# Apollo4-BluePlus-Module_rev_b_v7.net
KiCad netlist of a schematic drawn in EAGLE
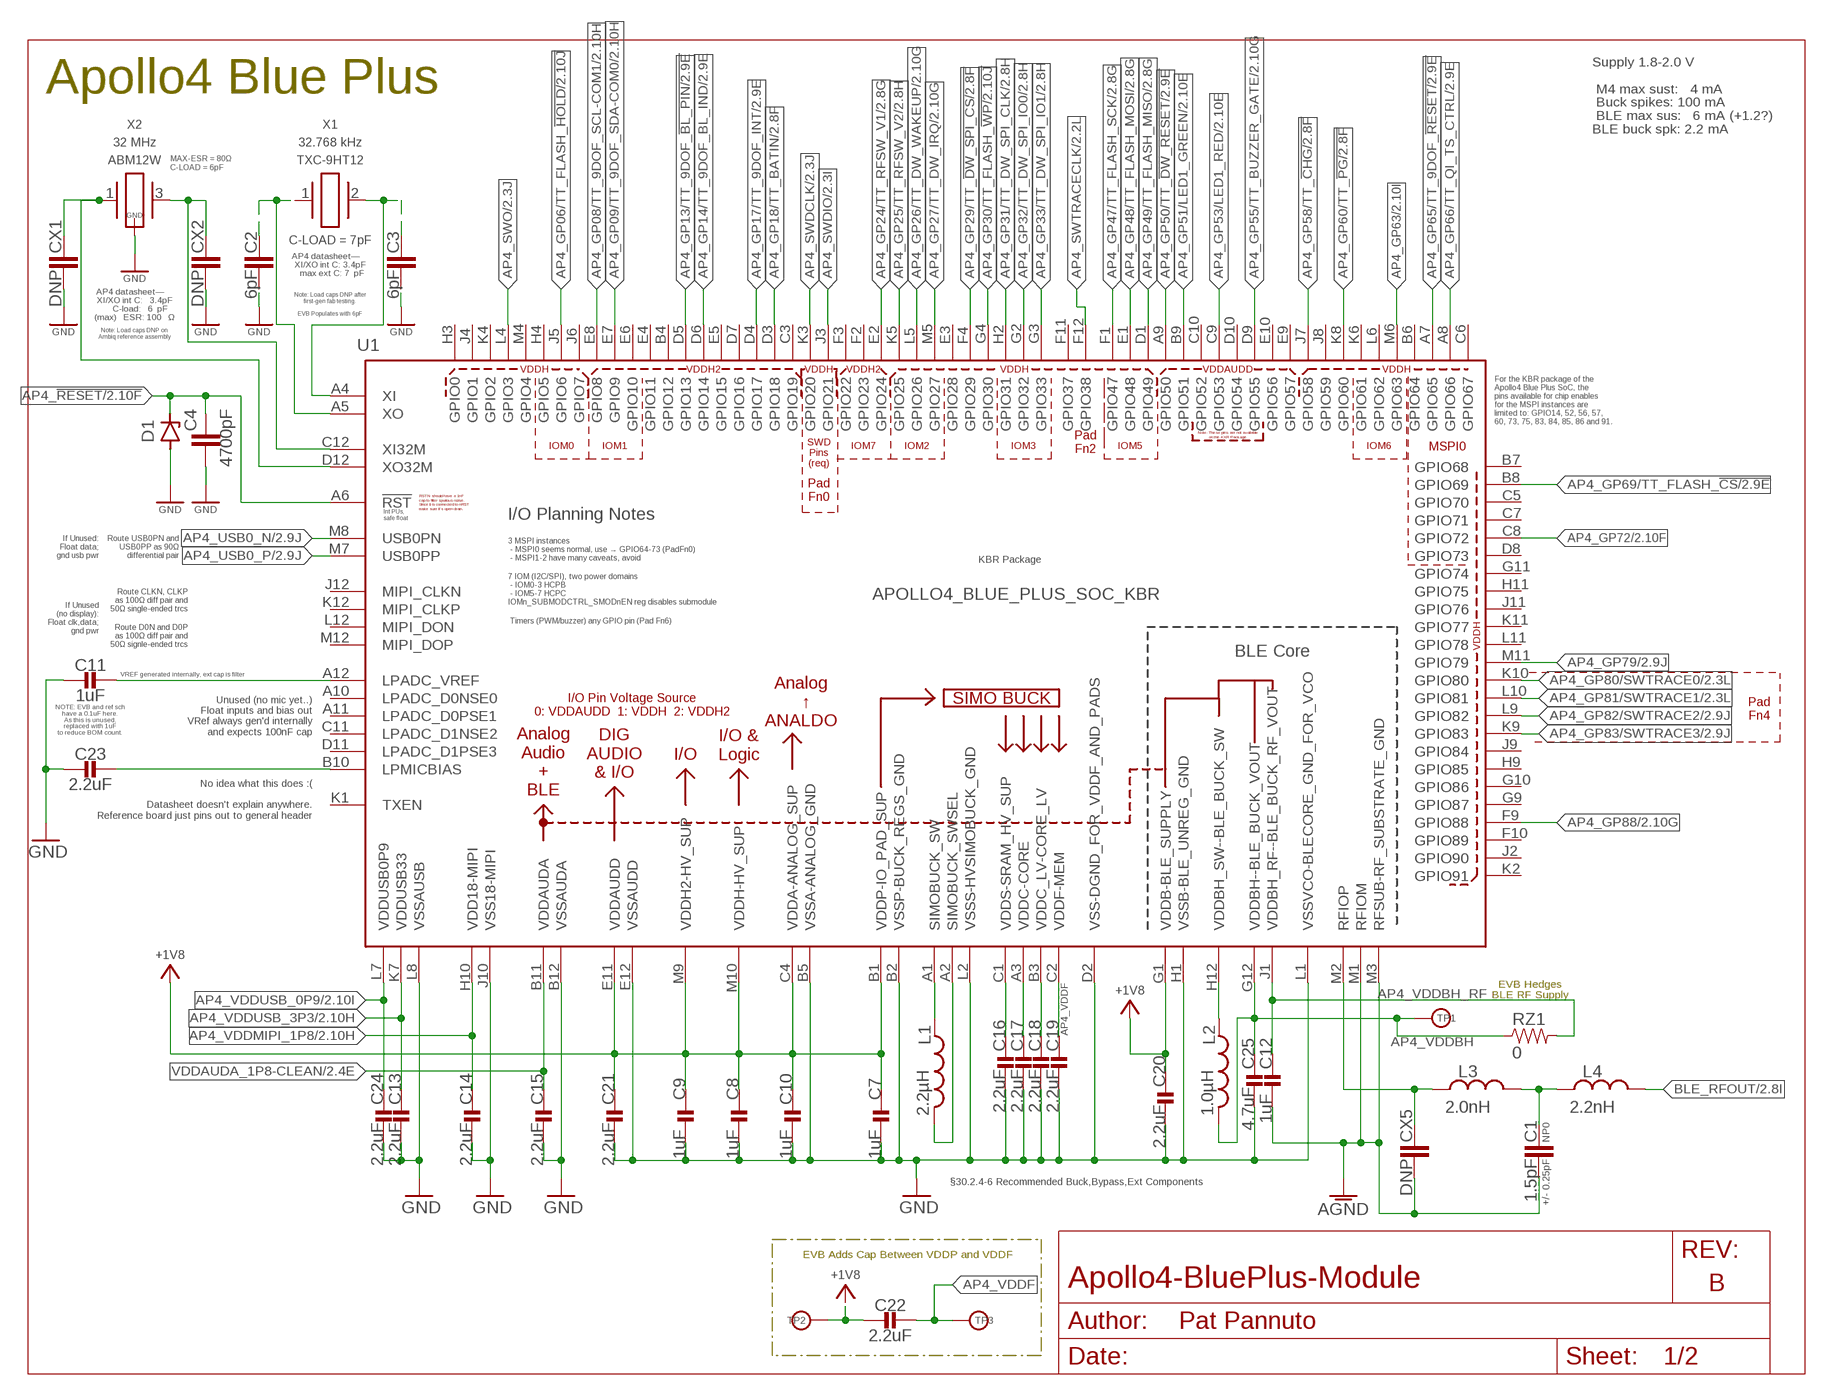
[diagram p0: schematic, sheet 1]
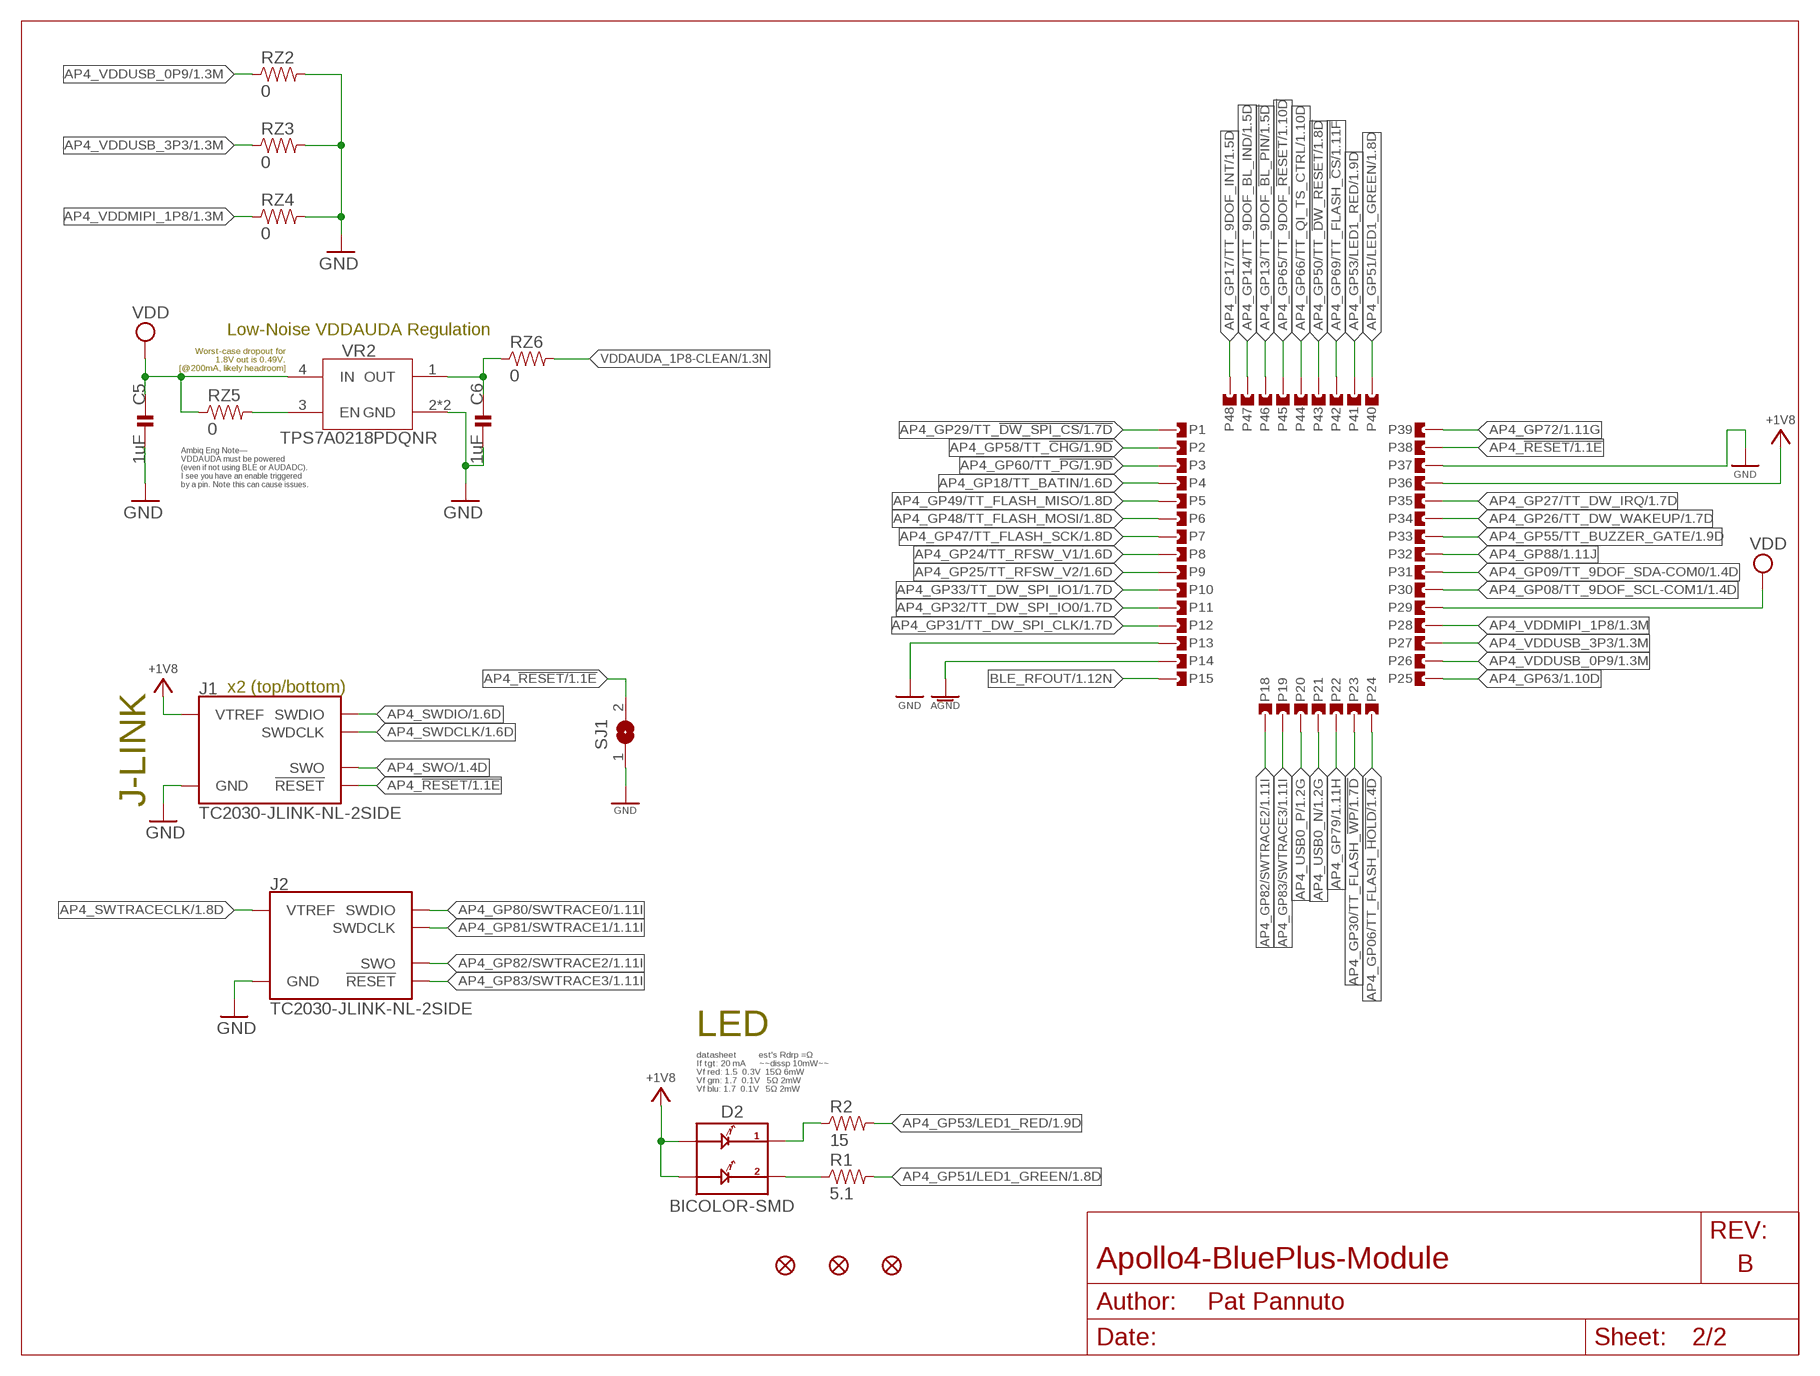
[diagram p1: schematic, sheet 2]

(export (version "E")
  (design (tool "Eeschema 10.0.6"))
  (components
    (comp (ref "C5")
      (value "1uF")
      (footprint "eagle-import:0201_CAP")
      (fields (field (name "MANUFACTURER") "Murata") (field (name "MPN") "GRM033R61A105ME44D"))
      (libsource (lib "eagle-import") (part "passives_20904581_CAPACITOR0201_CAP"))
    )
    (comp (ref "C6")
      (value "1uF")
      (footprint "eagle-import:0201_CAP")
      (fields (field (name "MANUFACTURER") "Murata") (field (name "MPN") "GRM033R61A105ME44D"))
      (libsource (lib "eagle-import") (part "passives_20904581_CAPACITOR0201_CAP"))
    )
    (comp (ref "D2")
      (value "BICOLOR-SMD")
      (footprint "eagle-import:LED-0606")
      (fields (field (name "MPN") "MCL0606FRD1GR1T"))
      (libsource (lib "eagle-import") (part "BICOLOR-SMD"))
    )
    (comp (ref "FD1")
      (value "FIDUCIALUFIDUCIAL")
      (footprint "eagle-import:FIDUCIAL-MICRO")
      (libsource (lib "eagle-import") (part "FIDUCIALUFIDUCIAL"))
    )
    (comp (ref "FD2")
      (value "FIDUCIALUFIDUCIAL")
      (footprint "eagle-import:FIDUCIAL-MICRO")
      (libsource (lib "eagle-import") (part "FIDUCIALUFIDUCIAL"))
    )
    (comp (ref "FD3")
      (value "FIDUCIALUFIDUCIAL")
      (footprint "eagle-import:FIDUCIAL-MICRO")
      (libsource (lib "eagle-import") (part "FIDUCIALUFIDUCIAL"))
    )
    (comp (ref "J1")
      (value "TC2030-JLINK-NL-2SIDE")
      (footprint "eagle-import:TC2030-IDC-NL-2SIDE")
      (libsource (lib "eagle-import") (part "TC2030-JLINK-NL-2SIDE"))
    )
    (comp (ref "J2")
      (value "TC2030-JLINK-NL-2SIDE")
      (footprint "eagle-import:TC2030-IDC-NL-2SIDE")
      (libsource (lib "eagle-import") (part "TC2030-JLINK-NL-2SIDE"))
    )
    (comp (ref "P1")
      (value "CASTELLATION4L")
      (footprint "eagle-import:CASTELLATION-0.55MM_DRILL-4L")
      (libsource (lib "eagle-import") (part "CASTELLATION4L"))
    )
    (comp (ref "P2")
      (value "CASTELLATION4L")
      (footprint "eagle-import:CASTELLATION-0.55MM_DRILL-4L")
      (libsource (lib "eagle-import") (part "CASTELLATION4L"))
    )
    (comp (ref "P3")
      (value "CASTELLATION4L")
      (footprint "eagle-import:CASTELLATION-0.55MM_DRILL-4L")
      (libsource (lib "eagle-import") (part "CASTELLATION4L"))
    )
    (comp (ref "P4")
      (value "CASTELLATION4L")
      (footprint "eagle-import:CASTELLATION-0.55MM_DRILL-4L")
      (libsource (lib "eagle-import") (part "CASTELLATION4L"))
    )
    (comp (ref "P5")
      (value "CASTELLATION4L")
      (footprint "eagle-import:CASTELLATION-0.55MM_DRILL-4L")
      (libsource (lib "eagle-import") (part "CASTELLATION4L"))
    )
    (comp (ref "P6")
      (value "CASTELLATION4L")
      (footprint "eagle-import:CASTELLATION-0.55MM_DRILL-4L")
      (libsource (lib "eagle-import") (part "CASTELLATION4L"))
    )
    (comp (ref "P7")
      (value "CASTELLATION4L")
      (footprint "eagle-import:CASTELLATION-0.55MM_DRILL-4L")
      (libsource (lib "eagle-import") (part "CASTELLATION4L"))
    )
    (comp (ref "P8")
      (value "CASTELLATION4L")
      (footprint "eagle-import:CASTELLATION-0.55MM_DRILL-4L")
      (libsource (lib "eagle-import") (part "CASTELLATION4L"))
    )
    (comp (ref "P9")
      (value "CASTELLATION4L")
      (footprint "eagle-import:CASTELLATION-0.55MM_DRILL-4L")
      (libsource (lib "eagle-import") (part "CASTELLATION4L"))
    )
    (comp (ref "P10")
      (value "CASTELLATION4L")
      (footprint "eagle-import:CASTELLATION-0.55MM_DRILL-4L")
      (libsource (lib "eagle-import") (part "CASTELLATION4L"))
    )
    (comp (ref "P11")
      (value "CASTELLATION4L")
      (footprint "eagle-import:CASTELLATION-0.55MM_DRILL-4L")
      (libsource (lib "eagle-import") (part "CASTELLATION4L"))
    )
    (comp (ref "P12")
      (value "CASTELLATION4L")
      (footprint "eagle-import:CASTELLATION-0.55MM_DRILL-4L")
      (libsource (lib "eagle-import") (part "CASTELLATION4L"))
    )
    (comp (ref "P13")
      (value "CASTELLATION4L")
      (footprint "eagle-import:CASTELLATION-0.55MM_DRILL-4L")
      (libsource (lib "eagle-import") (part "CASTELLATION4L"))
    )
    (comp (ref "P14")
      (value "CASTELLATION4L")
      (footprint "eagle-import:CASTELLATION-0.55MM_DRILL-4L")
      (libsource (lib "eagle-import") (part "CASTELLATION4L"))
    )
    (comp (ref "P15")
      (value "CASTELLATION4L")
      (footprint "eagle-import:CASTELLATION-0.55MM_DRILL-4L")
      (libsource (lib "eagle-import") (part "CASTELLATION4L"))
    )
    (comp (ref "P18")
      (value "CASTELLATION4L")
      (footprint "eagle-import:CASTELLATION-0.55MM_DRILL-4L")
      (libsource (lib "eagle-import") (part "CASTELLATION4L"))
    )
    (comp (ref "P19")
      (value "CASTELLATION4L")
      (footprint "eagle-import:CASTELLATION-0.55MM_DRILL-4L")
      (libsource (lib "eagle-import") (part "CASTELLATION4L"))
    )
    (comp (ref "P20")
      (value "CASTELLATION4L")
      (footprint "eagle-import:CASTELLATION-0.55MM_DRILL-4L")
      (libsource (lib "eagle-import") (part "CASTELLATION4L"))
    )
    (comp (ref "P21")
      (value "CASTELLATION4L")
      (footprint "eagle-import:CASTELLATION-0.55MM_DRILL-4L")
      (libsource (lib "eagle-import") (part "CASTELLATION4L"))
    )
    (comp (ref "P22")
      (value "CASTELLATION4L")
      (footprint "eagle-import:CASTELLATION-0.55MM_DRILL-4L")
      (libsource (lib "eagle-import") (part "CASTELLATION4L"))
    )
    (comp (ref "P23")
      (value "CASTELLATION4L")
      (footprint "eagle-import:CASTELLATION-0.55MM_DRILL-4L")
      (libsource (lib "eagle-import") (part "CASTELLATION4L"))
    )
    (comp (ref "P24")
      (value "CASTELLATION4L")
      (footprint "eagle-import:CASTELLATION-0.55MM_DRILL-4L")
      (libsource (lib "eagle-import") (part "CASTELLATION4L"))
    )
    (comp (ref "P25")
      (value "CASTELLATION4L")
      (footprint "eagle-import:CASTELLATION-0.55MM_DRILL-4L")
      (libsource (lib "eagle-import") (part "CASTELLATION4L"))
    )
    (comp (ref "P26")
      (value "CASTELLATION4L")
      (footprint "eagle-import:CASTELLATION-0.55MM_DRILL-4L")
      (libsource (lib "eagle-import") (part "CASTELLATION4L"))
    )
    (comp (ref "P27")
      (value "CASTELLATION4L")
      (footprint "eagle-import:CASTELLATION-0.55MM_DRILL-4L")
      (libsource (lib "eagle-import") (part "CASTELLATION4L"))
    )
    (comp (ref "P28")
      (value "CASTELLATION4L")
      (footprint "eagle-import:CASTELLATION-0.55MM_DRILL-4L")
      (libsource (lib "eagle-import") (part "CASTELLATION4L"))
    )
    (comp (ref "P29")
      (value "CASTELLATION4L")
      (footprint "eagle-import:CASTELLATION-0.55MM_DRILL-4L")
      (libsource (lib "eagle-import") (part "CASTELLATION4L"))
    )
    (comp (ref "P30")
      (value "CASTELLATION4L")
      (footprint "eagle-import:CASTELLATION-0.55MM_DRILL-4L")
      (libsource (lib "eagle-import") (part "CASTELLATION4L"))
    )
    (comp (ref "P31")
      (value "CASTELLATION4L")
      (footprint "eagle-import:CASTELLATION-0.55MM_DRILL-4L")
      (libsource (lib "eagle-import") (part "CASTELLATION4L"))
    )
    (comp (ref "P32")
      (value "CASTELLATION4L")
      (footprint "eagle-import:CASTELLATION-0.55MM_DRILL-4L")
      (libsource (lib "eagle-import") (part "CASTELLATION4L"))
    )
    (comp (ref "P33")
      (value "CASTELLATION4L")
      (footprint "eagle-import:CASTELLATION-0.55MM_DRILL-4L")
      (libsource (lib "eagle-import") (part "CASTELLATION4L"))
    )
    (comp (ref "P34")
      (value "CASTELLATION4L")
      (footprint "eagle-import:CASTELLATION-0.55MM_DRILL-4L")
      (libsource (lib "eagle-import") (part "CASTELLATION4L"))
    )
    (comp (ref "P35")
      (value "CASTELLATION4L")
      (footprint "eagle-import:CASTELLATION-0.55MM_DRILL-4L")
      (libsource (lib "eagle-import") (part "CASTELLATION4L"))
    )
    (comp (ref "P36")
      (value "CASTELLATION4L")
      (footprint "eagle-import:CASTELLATION-0.55MM_DRILL-4L")
      (libsource (lib "eagle-import") (part "CASTELLATION4L"))
    )
    (comp (ref "P37")
      (value "CASTELLATION4L")
      (footprint "eagle-import:CASTELLATION-0.55MM_DRILL-4L")
      (libsource (lib "eagle-import") (part "CASTELLATION4L"))
    )
    (comp (ref "P38")
      (value "CASTELLATION4L")
      (footprint "eagle-import:CASTELLATION-0.55MM_DRILL-4L")
      (libsource (lib "eagle-import") (part "CASTELLATION4L"))
    )
    (comp (ref "P39")
      (value "CASTELLATION4L")
      (footprint "eagle-import:CASTELLATION-0.55MM_DRILL-4L")
      (libsource (lib "eagle-import") (part "CASTELLATION4L"))
    )
    (comp (ref "P40")
      (value "CASTELLATION4L")
      (footprint "eagle-import:CASTELLATION-0.55MM_DRILL-4L")
      (libsource (lib "eagle-import") (part "CASTELLATION4L"))
    )
    (comp (ref "P41")
      (value "CASTELLATION4L")
      (footprint "eagle-import:CASTELLATION-0.55MM_DRILL-4L")
      (libsource (lib "eagle-import") (part "CASTELLATION4L"))
    )
    (comp (ref "P42")
      (value "CASTELLATION4L")
      (footprint "eagle-import:CASTELLATION-0.55MM_DRILL-4L")
      (libsource (lib "eagle-import") (part "CASTELLATION4L"))
    )
    (comp (ref "P43")
      (value "CASTELLATION4L")
      (footprint "eagle-import:CASTELLATION-0.55MM_DRILL-4L")
      (libsource (lib "eagle-import") (part "CASTELLATION4L"))
    )
    (comp (ref "P44")
      (value "CASTELLATION4L")
      (footprint "eagle-import:CASTELLATION-0.55MM_DRILL-4L")
      (libsource (lib "eagle-import") (part "CASTELLATION4L"))
    )
    (comp (ref "P45")
      (value "CASTELLATION4L")
      (footprint "eagle-import:CASTELLATION-0.55MM_DRILL-4L")
      (libsource (lib "eagle-import") (part "CASTELLATION4L"))
    )
    (comp (ref "P46")
      (value "CASTELLATION4L")
      (footprint "eagle-import:CASTELLATION-0.55MM_DRILL-4L")
      (libsource (lib "eagle-import") (part "CASTELLATION4L"))
    )
    (comp (ref "P47")
      (value "CASTELLATION4L")
      (footprint "eagle-import:CASTELLATION-0.55MM_DRILL-4L")
      (libsource (lib "eagle-import") (part "CASTELLATION4L"))
    )
    (comp (ref "P48")
      (value "CASTELLATION4L")
      (footprint "eagle-import:CASTELLATION-0.55MM_DRILL-4L")
      (libsource (lib "eagle-import") (part "CASTELLATION4L"))
    )
    (comp (ref "R1")
      (value "5.1")
      (footprint "eagle-import:0201_RES")
      (fields (field (name "MPN") "SR731HTTC5R10F"))
      (libsource (lib "eagle-import") (part "RESISTOR0201_RES"))
    )
    (comp (ref "R2")
      (value "15")
      (footprint "eagle-import:0201_RES")
      (description "RES SMD 15 OHM 5% 1/20W 0201")
      (fields (field (name "MPN") "ERJ-1GNJ150C"))
      (libsource (lib "eagle-import") (part "RESISTOR0201_RES"))
    )
    (comp (ref "RZ2")
      (value "0")
      (footprint "eagle-import:0402_RES")
      (fields (field (name "MPN") "RMCF0402ZT0R00"))
      (libsource (lib "eagle-import") (part "RESISTOR0402_RES"))
    )
    (comp (ref "RZ3")
      (value "0")
      (footprint "eagle-import:0402_RES")
      (fields (field (name "MPN") "RMCF0402ZT0R00"))
      (libsource (lib "eagle-import") (part "RESISTOR0402_RES"))
    )
    (comp (ref "RZ4")
      (value "0")
      (footprint "eagle-import:0402_RES")
      (fields (field (name "MPN") "RMCF0402ZT0R00"))
      (libsource (lib "eagle-import") (part "RESISTOR0402_RES"))
    )
    (comp (ref "RZ5")
      (value "0")
      (footprint "eagle-import:0402_RES")
      (fields (field (name "MPN") "RMCF0402ZT0R00"))
      (libsource (lib "eagle-import") (part "RESISTOR0402_RES"))
    )
    (comp (ref "RZ6")
      (value "0")
      (footprint "eagle-import:0402_RES")
      (fields (field (name "MPN") "RMCF0402ZT0R00"))
      (libsource (lib "eagle-import") (part "RESISTOR0402_RES"))
    )
    (comp (ref "SJ1") (value "SJ") (footprint "eagle-import:SJ") (libsource (lib "eagle-import") (part "SJ")))
    (comp (ref "VR2")
      (value "TPS7A0218PDQNR")
      (footprint "eagle-import:4-XDFN-EP")
      (libsource (lib "eagle-import") (part "TPS7A0218PDQNR"))
    )
    (comp (ref "C1")
      (value "1.5pF")
      (footprint "eagle-import:CAPC1005X60")
      (description "CAP CER 1.5PF 50V C0G/NP0 0402")
      (fields
        (field (name "MANUFACTURER") "KEMET")
        (field (name "MPN") "C0402C159C5GAC7867")
        (field (name "TEMPCOEFF") "NP0")
        (field (name "TOLERANCE") "+/- 0.25pF")
      )
      (libsource (lib "eagle-import") (part "CCHIP-0402(1005-METRIC)_"))
    )
    (comp (ref "C2")
      (value "6pF")
      (footprint "eagle-import:CAPC1005X60")
      (fields (field (name "MANUFACTURER") "Murata") (field (name "MPN") "GCM1555C1H6R0BA16D"))
      (libsource (lib "eagle-import") (part "CCHIP-0402(1005-METRIC)_"))
    )
    (comp (ref "C3")
      (value "6pF")
      (footprint "eagle-import:CAPC1005X60")
      (fields (field (name "MANUFACTURER") "Murata") (field (name "MPN") "GCM1555C1H6R0BA16D"))
      (libsource (lib "eagle-import") (part "CCHIP-0402(1005-METRIC)_"))
    )
    (comp (ref "C4")
      (value "4700pF")
      (footprint "eagle-import:CAPC1005X60")
      (fields (field (name "MPN") "KGM05AR71E472KH"))
      (libsource (lib "eagle-import") (part "CCHIP-0402(1005-METRIC)_"))
    )
    (comp (ref "C7")
      (value "1uF")
      (footprint "eagle-import:0201_CAP")
      (fields (field (name "MANUFACTURER") "Murata") (field (name "MPN") "GRM033R61A105ME44D"))
      (libsource (lib "eagle-import") (part "passives_20904581_CAPACITOR0201_CAP"))
    )
    (comp (ref "C8")
      (value "1uF")
      (footprint "eagle-import:0201_CAP")
      (fields (field (name "MANUFACTURER") "Murata") (field (name "MPN") "GRM033R61A105ME44D"))
      (libsource (lib "eagle-import") (part "passives_20904581_CAPACITOR0201_CAP"))
    )
    (comp (ref "C9")
      (value "1uF")
      (footprint "eagle-import:0201_CAP")
      (fields (field (name "MANUFACTURER") "Murata") (field (name "MPN") "GRM033R61A105ME44D"))
      (libsource (lib "eagle-import") (part "passives_20904581_CAPACITOR0201_CAP"))
    )
    (comp (ref "C10")
      (value "1uF")
      (footprint "eagle-import:0201_CAP")
      (fields (field (name "MANUFACTURER") "Murata") (field (name "MPN") "GRM033R61A105ME44D"))
      (libsource (lib "eagle-import") (part "passives_20904581_CAPACITOR0201_CAP"))
    )
    (comp (ref "C11")
      (value "1uF")
      (footprint "eagle-import:0201_CAP")
      (fields (field (name "MANUFACTURER") "MURATA") (field (name "MPN") "GRM033R61A105ME44D"))
      (libsource (lib "eagle-import") (part "passives_20904581_CAPACITOR0201_CAP"))
    )
    (comp (ref "C12")
      (value "1uF")
      (footprint "eagle-import:0201_CAP")
      (fields (field (name "MANUFACTURER") "Murata") (field (name "MPN") "GRM033R61A105ME44D"))
      (libsource (lib "eagle-import") (part "passives_20904581_CAPACITOR0201_CAP"))
    )
    (comp (ref "C13")
      (value "2.2uF")
      (footprint "eagle-import:0201_CAP")
      (fields (field (name "MANUFACTURER") "Murata") (field (name "MPN") "GRM033R61A225KE47D"))
      (libsource (lib "eagle-import") (part "passives_20904581_CAPACITOR0201_CAP"))
    )
    (comp (ref "C14")
      (value "2.2uF")
      (footprint "eagle-import:0201_CAP")
      (fields (field (name "MANUFACTURER") "Murata") (field (name "MPN") "GRM033R61A225KE47D"))
      (libsource (lib "eagle-import") (part "passives_20904581_CAPACITOR0201_CAP"))
    )
    (comp (ref "C15")
      (value "2.2uF")
      (footprint "eagle-import:0201_CAP")
      (fields (field (name "MANUFACTURER") "Murata") (field (name "MPN") "GRM033R61A225KE47D"))
      (libsource (lib "eagle-import") (part "passives_20904581_CAPACITOR0201_CAP"))
    )
    (comp (ref "C16")
      (value "2.2uF")
      (footprint "eagle-import:0201_CAP")
      (fields (field (name "MANUFACTURER") "Murata") (field (name "MPN") "GRM033R61A225KE47D"))
      (libsource (lib "eagle-import") (part "passives_20904581_CAPACITOR0201_CAP"))
    )
    (comp (ref "C17")
      (value "2.2uF")
      (footprint "eagle-import:0201_CAP")
      (fields (field (name "MANUFACTURER") "Murata") (field (name "MPN") "GRM033R61A225KE47D"))
      (libsource (lib "eagle-import") (part "passives_20904581_CAPACITOR0201_CAP"))
    )
    (comp (ref "C18")
      (value "2.2uF")
      (footprint "eagle-import:0201_CAP")
      (fields (field (name "MANUFACTURER") "Murata") (field (name "MPN") "GRM033R61A225KE47D"))
      (libsource (lib "eagle-import") (part "passives_20904581_CAPACITOR0201_CAP"))
    )
    (comp (ref "C19")
      (value "2.2uF")
      (footprint "eagle-import:0201_CAP")
      (fields (field (name "MANUFACTURER") "Murata") (field (name "MPN") "GRM033R61A225KE47D"))
      (libsource (lib "eagle-import") (part "passives_20904581_CAPACITOR0201_CAP"))
    )
    (comp (ref "C20")
      (value "2.2uF")
      (footprint "eagle-import:0201_CAP")
      (fields (field (name "MANUFACTURER") "Murata") (field (name "MPN") "GRM033R61A225KE47D"))
      (libsource (lib "eagle-import") (part "passives_20904581_CAPACITOR0201_CAP"))
    )
    (comp (ref "C21")
      (value "2.2uF")
      (footprint "eagle-import:0201_CAP")
      (fields (field (name "MANUFACTURER") "Murata") (field (name "MPN") "GRM033R61A225KE47D"))
      (libsource (lib "eagle-import") (part "passives_20904581_CAPACITOR0201_CAP"))
    )
    (comp (ref "C22")
      (value "2.2uF")
      (footprint "eagle-import:0201_CAP")
      (fields (field (name "MANUFACTURER") "Murata") (field (name "MPN") "GRM033R61A225KE47D"))
      (libsource (lib "eagle-import") (part "passives_20904581_CAPACITOR0201_CAP"))
    )
    (comp (ref "C23")
      (value "2.2uF")
      (footprint "eagle-import:0201_CAP")
      (fields (field (name "MANUFACTURER") "Murata") (field (name "MPN") "GRM033R61A225KE47D"))
      (libsource (lib "eagle-import") (part "passives_20904581_CAPACITOR0201_CAP"))
    )
    (comp (ref "C24")
      (value "2.2uF")
      (footprint "eagle-import:0201_CAP")
      (fields (field (name "MANUFACTURER") "Murata") (field (name "MPN") "GRM033R61A225KE47D"))
      (libsource (lib "eagle-import") (part "passives_20904581_CAPACITOR0201_CAP"))
    )
    (comp (ref "C25")
      (value "4.7uF")
      (footprint "eagle-import:0402_CAP")
      (fields (field (name "MPN") "CL05A475MP5NRNC"))
      (libsource (lib "eagle-import") (part "CAPACITOR0402_CAP"))
    )
    (comp (ref "CX1")
      (value "DNP")
      (footprint "eagle-import:CAPC1005X60")
      (libsource (lib "eagle-import") (part "CCHIP-0402(1005-METRIC)_"))
    )
    (comp (ref "CX2")
      (value "DNP")
      (footprint "eagle-import:CAPC1005X60")
      (libsource (lib "eagle-import") (part "CCHIP-0402(1005-METRIC)_"))
    )
    (comp (ref "CX5")
      (value "DNP")
      (footprint "eagle-import:CAPC1005X60")
      (libsource (lib "eagle-import") (part "CCHIP-0402(1005-METRIC)_"))
    )
    (comp (ref "D1")
      (value "ZENER")
      (footprint "eagle-import:SODFL1608X70")
      (description "DIODE TVS 5.5V STANDOFF 8V BREAKDOWN SC79")
      (fields (field (name "MANUFACTURER") "NXP SEMICONDUCTOR") (field (name "MPN") "PESD5V0X1UB,135"))
      (libsource (lib "eagle-import") (part "ZENERSODFL(1608-METRIC)_"))
    )
    (comp (ref "L1")
      (value "2.2µH")
      (footprint "eagle-import:0805_CAP")
      (fields (field (name "MANUFACTURER") "Murata") (field (name "MPN") "DFE201210U-2R2M=P2"))
      (libsource (lib "eagle-import") (part "INDUCTOR0805"))
    )
    (comp (ref "L2")
      (value "1.0µH")
      (footprint "eagle-import:0603_CAP")
      (fields (field (name "MANUFACTURER") "Murata") (field (name "MPN") "DFE18SAN1R0ME0L"))
      (libsource (lib "eagle-import") (part "INDUCTOR0603"))
    )
    (comp (ref "L3")
      (value "2.0nH")
      (footprint "eagle-import:INDC1006X60N")
      (description "FIXED IND 2.0NH0.1NH SMD")
      (fields
        (field (name "MANUFACTURER") "Central Technologies")
        (field (name "MPN") "CTTF0402F-2N0B")
        (field (name "TOLERANCE") "+/- 0.1 nH")
      )
      (libsource (lib "eagle-import") (part "LCHIP-0402(1006-METRIC)_"))
    )
    (comp (ref "L4")
      (value "2.2nH")
      (footprint "eagle-import:INDC1006X60N")
      (description "FIXED IND 2.2NH0.1NH SMD")
      (fields
        (field (name "MANUFACTURER") "Central Technologies")
        (field (name "MPN") "CTTF0402F-2N2B")
        (field (name "TOLERANCE") "+/- 0.1 nH")
      )
      (libsource (lib "eagle-import") (part "LCHIP-0402(1006-METRIC)_"))
    )
    (comp (ref "RZ1")
      (value "0")
      (footprint "eagle-import:0402_RES")
      (fields (field (name "MPN") "RMCF0402ZT0R00"))
      (libsource (lib "eagle-import") (part "RESISTOR0402_RES"))
    )
    (comp (ref "TP1")
      (value "VDDBH")
      (footprint "eagle-import:PAD.03X.03")
      (libsource (lib "eagle-import") (part "TEST-POINT"))
    )
    (comp (ref "TP2")
      (value "VDDP")
      (footprint "eagle-import:PAD.03X.03")
      (libsource (lib "eagle-import") (part "TEST-POINT"))
    )
    (comp (ref "TP3")
      (value "VDDF")
      (footprint "eagle-import:PAD.03X.03")
      (libsource (lib "eagle-import") (part "TEST-POINT"))
    )
    (comp (ref "U1")
      (value "APOLLO4_BLUE_PLUS_SOC_KBR")
      (footprint "eagle-import:APOLLO4_BLUE_SOC_BGA")
      (fields (field (name "MANUFACTURER") "Ambiq") (field (name "MPN") "AMA4B2KP-KBR"))
      (libsource (lib "eagle-import") (part "APOLLO4_BLUE_PLUS_SOC_KBR"))
    )
    (comp (ref "X1")
      (value "TXC-9HT12")
      (footprint "eagle-import:TXC-9HT12")
      (fields
        (field (name "C-LOAD") "7pF")
        (field (name "FREQUENCY") "32.768 kHz")
        (field (name "MANUFACTURER") "TXC Corp")
        (field (name "MPN") "9HT12-32.768KDZY-T")
      )
      (libsource (lib "eagle-import") (part "TXC-9HT12"))
    )
    (comp (ref "X2")
      (value "ABM12W")
      (footprint "eagle-import:ABM12W")
      (fields
        (field (name "C-LOAD") "6pF")
        (field (name "FREQUENCY") "32 MHz")
        (field (name "MANUFACTURER") "Abracon")
        (field (name "MAX-ESR") "80Ω")
        (field (name "MPN") "ABM12W-32.0000MHZ-6-D1X-T3")
      )
      (libsource (lib "eagle-import") (part "ABM12W"))
    )
  )
  (nets
    (net (code "1") (name "+1V8") (class "Default")
      (node (ref "C10") (pin "P$1") (pinfunction "1_P$1") (pintype "bidirectional"))
      (node (ref "C20") (pin "P$1") (pinfunction "1_P$1") (pintype "bidirectional"))
      (node (ref "C21") (pin "P$1") (pinfunction "1_P$1") (pintype "bidirectional"))
      (node (ref "C22") (pin "P$2") (pinfunction "2_P$2") (pintype "bidirectional"))
      (node (ref "C7") (pin "P$1") (pinfunction "1_P$1") (pintype "bidirectional"))
      (node (ref "C8") (pin "P$1") (pinfunction "1_P$1") (pintype "bidirectional"))
      (node (ref "C9") (pin "P$1") (pinfunction "1_P$1") (pintype "bidirectional"))
      (node (ref "D2") (pin "A1") (pinfunction "A1_A1") (pintype "bidirectional"))
      (node (ref "D2") (pin "A2") (pinfunction "A2_A2") (pintype "bidirectional"))
      (node (ref "J1") (pin "1") (pinfunction "VTREF_1") (pintype "bidirectional"))
      (node (ref "J1") (pin "B1") (pinfunction "VTREF_B1") (pintype "bidirectional"))
      (node (ref "P36") (pin "P$1") (pinfunction "P$1_P$1") (pintype "bidirectional"))
      (node (ref "P36") (pin "P$2") (pinfunction "P$1_P$2") (pintype "bidirectional"))
      (node (ref "P36") (pin "P$3") (pinfunction "P$1_P$3") (pintype "bidirectional"))
      (node (ref "TP2") (pin "P$1") (pinfunction "TESTPOINT_P$1") (pintype "bidirectional"))
      (node (ref "U1") (pin "B1") (pinfunction "VDDP-IO_PAD_SUP_B1") (pintype "bidirectional"))
      (node (ref "U1") (pin "C4") (pinfunction "VDDA-ANALOG_SUP_C4") (pintype "bidirectional"))
      (node (ref "U1") (pin "E11") (pinfunction "VDDAUDD_E11") (pintype "bidirectional"))
      (node (ref "U1") (pin "G1") (pinfunction "VDDB-BLE_SUPPLY_G1") (pintype "bidirectional"))
      (node (ref "U1") (pin "M10") (pinfunction "VDDH-HV_SUP_M10") (pintype "bidirectional"))
      (node (ref "U1") (pin "M9") (pinfunction "VDDH2-HV_SUP_M9") (pintype "bidirectional"))
    )
    (net (code "2") (name "AGND") (class "Default")
      (node (ref "C1") (pin "2") (pinfunction "2_2") (pintype "passive"))
      (node (ref "C12") (pin "P$2") (pinfunction "2_P$2") (pintype "bidirectional"))
      (node (ref "CX5") (pin "2") (pinfunction "2_2") (pintype "passive"))
      (node (ref "P14") (pin "P$1") (pinfunction "P$1_P$1") (pintype "bidirectional"))
      (node (ref "P14") (pin "P$2") (pinfunction "P$1_P$2") (pintype "bidirectional"))
      (node (ref "P14") (pin "P$3") (pinfunction "P$1_P$3") (pintype "bidirectional"))
      (node (ref "U1") (pin "M1") (pinfunction "RFIOM_M1") (pintype "bidirectional"))
      (node (ref "U1") (pin "M3") (pinfunction "RFSUB-RF_SUBSTRATE_GND_M3") (pintype "bidirectional"))
    )
    (net (code "3") (name "AP4_GP06{slash}TT_FLASH_~{HOLD}") (class "Default")
      (node (ref "P24") (pin "P$1") (pinfunction "P$1_P$1") (pintype "bidirectional"))
      (node (ref "P24") (pin "P$2") (pinfunction "P$1_P$2") (pintype "bidirectional"))
      (node (ref "P24") (pin "P$3") (pinfunction "P$1_P$3") (pintype "bidirectional"))
      (node (ref "U1") (pin "J5") (pinfunction "GPIO6_J5") (pintype "bidirectional"))
    )
    (net (code "4") (name "AP4_GP08{slash}TT_9DOF_SCL-COM1") (class "Default")
      (node (ref "P30") (pin "P$1") (pinfunction "P$1_P$1") (pintype "bidirectional"))
      (node (ref "P30") (pin "P$2") (pinfunction "P$1_P$2") (pintype "bidirectional"))
      (node (ref "P30") (pin "P$3") (pinfunction "P$1_P$3") (pintype "bidirectional"))
      (node (ref "U1") (pin "E8") (pinfunction "GPIO8_E8") (pintype "bidirectional"))
    )
    (net (code "5") (name "AP4_GP09{slash}TT_9DOF_SDA-COM0") (class "Default")
      (node (ref "P31") (pin "P$1") (pinfunction "P$1_P$1") (pintype "bidirectional"))
      (node (ref "P31") (pin "P$2") (pinfunction "P$1_P$2") (pintype "bidirectional"))
      (node (ref "P31") (pin "P$3") (pinfunction "P$1_P$3") (pintype "bidirectional"))
      (node (ref "U1") (pin "E7") (pinfunction "GPIO9_E7") (pintype "bidirectional"))
    )
    (net (code "6") (name "AP4_GP13{slash}TT_9DOF_~{BL_PIN}") (class "Default")
      (node (ref "P46") (pin "P$1") (pinfunction "P$1_P$1") (pintype "bidirectional"))
      (node (ref "P46") (pin "P$2") (pinfunction "P$1_P$2") (pintype "bidirectional"))
      (node (ref "P46") (pin "P$3") (pinfunction "P$1_P$3") (pintype "bidirectional"))
      (node (ref "U1") (pin "D5") (pinfunction "GPIO13_D5") (pintype "bidirectional"))
    )
    (net (code "7") (name "AP4_GP14{slash}TT_9DOF_BL_IND") (class "Default")
      (node (ref "P47") (pin "P$1") (pinfunction "P$1_P$1") (pintype "bidirectional"))
      (node (ref "P47") (pin "P$2") (pinfunction "P$1_P$2") (pintype "bidirectional"))
      (node (ref "P47") (pin "P$3") (pinfunction "P$1_P$3") (pintype "bidirectional"))
      (node (ref "U1") (pin "D6") (pinfunction "GPIO14_D6") (pintype "bidirectional"))
    )
    (net (code "8") (name "AP4_GP17{slash}TT_9DOF_INT") (class "Default")
      (node (ref "P48") (pin "P$1") (pinfunction "P$1_P$1") (pintype "bidirectional"))
      (node (ref "P48") (pin "P$2") (pinfunction "P$1_P$2") (pintype "bidirectional"))
      (node (ref "P48") (pin "P$3") (pinfunction "P$1_P$3") (pintype "bidirectional"))
      (node (ref "U1") (pin "D4") (pinfunction "GPIO17_D4") (pintype "bidirectional"))
    )
    (net (code "9") (name "AP4_GP18{slash}TT_BATIN") (class "Default")
      (node (ref "P4") (pin "P$1") (pinfunction "P$1_P$1") (pintype "bidirectional"))
      (node (ref "P4") (pin "P$2") (pinfunction "P$1_P$2") (pintype "bidirectional"))
      (node (ref "P4") (pin "P$3") (pinfunction "P$1_P$3") (pintype "bidirectional"))
      (node (ref "U1") (pin "D3") (pinfunction "GPIO18_D3") (pintype "bidirectional"))
    )
    (net (code "10") (name "AP4_GP24{slash}TT_RFSW_V1") (class "Default")
      (node (ref "P8") (pin "P$1") (pinfunction "P$1_P$1") (pintype "bidirectional"))
      (node (ref "P8") (pin "P$2") (pinfunction "P$1_P$2") (pintype "bidirectional"))
      (node (ref "P8") (pin "P$3") (pinfunction "P$1_P$3") (pintype "bidirectional"))
      (node (ref "U1") (pin "E2") (pinfunction "GPIO24_E2") (pintype "bidirectional"))
    )
    (net (code "11") (name "AP4_GP25{slash}TT_RFSW_V2") (class "Default")
      (node (ref "P9") (pin "P$1") (pinfunction "P$1_P$1") (pintype "bidirectional"))
      (node (ref "P9") (pin "P$2") (pinfunction "P$1_P$2") (pintype "bidirectional"))
      (node (ref "P9") (pin "P$3") (pinfunction "P$1_P$3") (pintype "bidirectional"))
      (node (ref "U1") (pin "K5") (pinfunction "GPIO25_K5") (pintype "bidirectional"))
    )
    (net (code "12") (name "AP4_GP26{slash}TT_DW_WAKEUP") (class "Default")
      (node (ref "P34") (pin "P$1") (pinfunction "P$1_P$1") (pintype "bidirectional"))
      (node (ref "P34") (pin "P$2") (pinfunction "P$1_P$2") (pintype "bidirectional"))
      (node (ref "P34") (pin "P$3") (pinfunction "P$1_P$3") (pintype "bidirectional"))
      (node (ref "U1") (pin "L5") (pinfunction "GPIO26_L5") (pintype "bidirectional"))
    )
    (net (code "13") (name "AP4_GP27{slash}TT_DW_IRQ") (class "Default")
      (node (ref "P35") (pin "P$1") (pinfunction "P$1_P$1") (pintype "bidirectional"))
      (node (ref "P35") (pin "P$2") (pinfunction "P$1_P$2") (pintype "bidirectional"))
      (node (ref "P35") (pin "P$3") (pinfunction "P$1_P$3") (pintype "bidirectional"))
      (node (ref "U1") (pin "M5") (pinfunction "GPIO27_M5") (pintype "bidirectional"))
    )
    (net (code "14") (name "AP4_GP29{slash}TT_~{DW_SPI_CS}") (class "Default")
      (node (ref "P1") (pin "P$1") (pinfunction "P$1_P$1") (pintype "bidirectional"))
      (node (ref "P1") (pin "P$2") (pinfunction "P$1_P$2") (pintype "bidirectional"))
      (node (ref "P1") (pin "P$3") (pinfunction "P$1_P$3") (pintype "bidirectional"))
      (node (ref "U1") (pin "F4") (pinfunction "GPIO29_F4") (pintype "bidirectional"))
    )
    (net (code "15") (name "AP4_GP30{slash}TT_FLASH_~{WP}") (class "Default")
      (node (ref "P23") (pin "P$1") (pinfunction "P$1_P$1") (pintype "bidirectional"))
      (node (ref "P23") (pin "P$2") (pinfunction "P$1_P$2") (pintype "bidirectional"))
      (node (ref "P23") (pin "P$3") (pinfunction "P$1_P$3") (pintype "bidirectional"))
      (node (ref "U1") (pin "G4") (pinfunction "GPIO30_G4") (pintype "bidirectional"))
    )
    (net (code "16") (name "AP4_GP31{slash}TT_DW_SPI_CLK") (class "Default")
      (node (ref "P12") (pin "P$1") (pinfunction "P$1_P$1") (pintype "bidirectional"))
      (node (ref "P12") (pin "P$2") (pinfunction "P$1_P$2") (pintype "bidirectional"))
      (node (ref "P12") (pin "P$3") (pinfunction "P$1_P$3") (pintype "bidirectional"))
      (node (ref "U1") (pin "H2") (pinfunction "GPIO31_H2") (pintype "bidirectional"))
    )
    (net (code "17") (name "AP4_GP32{slash}TT_DW_SPI_IO0") (class "Default")
      (node (ref "P11") (pin "P$1") (pinfunction "P$1_P$1") (pintype "bidirectional"))
      (node (ref "P11") (pin "P$2") (pinfunction "P$1_P$2") (pintype "bidirectional"))
      (node (ref "P11") (pin "P$3") (pinfunction "P$1_P$3") (pintype "bidirectional"))
      (node (ref "U1") (pin "G2") (pinfunction "GPIO32_G2") (pintype "bidirectional"))
    )
    (net (code "18") (name "AP4_GP33{slash}TT_DW_SPI_IO1") (class "Default")
      (node (ref "P10") (pin "P$1") (pinfunction "P$1_P$1") (pintype "bidirectional"))
      (node (ref "P10") (pin "P$2") (pinfunction "P$1_P$2") (pintype "bidirectional"))
      (node (ref "P10") (pin "P$3") (pinfunction "P$1_P$3") (pintype "bidirectional"))
      (node (ref "U1") (pin "G3") (pinfunction "GPIO33_G3") (pintype "bidirectional"))
    )
    (net (code "19") (name "AP4_GP47{slash}TT_FLASH_SCK") (class "Default")
      (node (ref "P7") (pin "P$1") (pinfunction "P$1_P$1") (pintype "bidirectional"))
      (node (ref "P7") (pin "P$2") (pinfunction "P$1_P$2") (pintype "bidirectional"))
      (node (ref "P7") (pin "P$3") (pinfunction "P$1_P$3") (pintype "bidirectional"))
      (node (ref "U1") (pin "F1") (pinfunction "GPIO47_F1") (pintype "bidirectional"))
    )
    (net (code "20") (name "AP4_GP48{slash}TT_FLASH_MOSI") (class "Default")
      (node (ref "P6") (pin "P$1") (pinfunction "P$1_P$1") (pintype "bidirectional"))
      (node (ref "P6") (pin "P$2") (pinfunction "P$1_P$2") (pintype "bidirectional"))
      (node (ref "P6") (pin "P$3") (pinfunction "P$1_P$3") (pintype "bidirectional"))
      (node (ref "U1") (pin "E1") (pinfunction "GPIO48_E1") (pintype "bidirectional"))
    )
    (net (code "21") (name "AP4_GP49{slash}TT_FLASH_MISO") (class "Default")
      (node (ref "P5") (pin "P$1") (pinfunction "P$1_P$1") (pintype "bidirectional"))
      (node (ref "P5") (pin "P$2") (pinfunction "P$1_P$2") (pintype "bidirectional"))
      (node (ref "P5") (pin "P$3") (pinfunction "P$1_P$3") (pintype "bidirectional"))
      (node (ref "U1") (pin "D1") (pinfunction "GPIO49_D1") (pintype "bidirectional"))
    )
    (net (code "22") (name "AP4_GP50{slash}TT_~{DW_RESET}") (class "Default")
      (node (ref "P43") (pin "P$1") (pinfunction "P$1_P$1") (pintype "bidirectional"))
      (node (ref "P43") (pin "P$2") (pinfunction "P$1_P$2") (pintype "bidirectional"))
      (node (ref "P43") (pin "P$3") (pinfunction "P$1_P$3") (pintype "bidirectional"))
      (node (ref "U1") (pin "A9") (pinfunction "GPIO50_A9") (pintype "bidirectional"))
    )
    (net (code "23") (name "AP4_GP51{slash}LED1_GREEN") (class "Default")
      (node (ref "P40") (pin "P$1") (pinfunction "P$1_P$1") (pintype "bidirectional"))
      (node (ref "P40") (pin "P$2") (pinfunction "P$1_P$2") (pintype "bidirectional"))
      (node (ref "P40") (pin "P$3") (pinfunction "P$1_P$3") (pintype "bidirectional"))
      (node (ref "R1") (pin "2") (pinfunction "2_2") (pintype "passive"))
      (node (ref "U1") (pin "B9") (pinfunction "GPIO51_B9") (pintype "bidirectional"))
    )
    (net (code "24") (name "AP4_GP53{slash}LED1_RED") (class "Default")
      (node (ref "P41") (pin "P$1") (pinfunction "P$1_P$1") (pintype "bidirectional"))
      (node (ref "P41") (pin "P$2") (pinfunction "P$1_P$2") (pintype "bidirectional"))
      (node (ref "P41") (pin "P$3") (pinfunction "P$1_P$3") (pintype "bidirectional"))
      (node (ref "R2") (pin "2") (pinfunction "2_2") (pintype "passive"))
      (node (ref "U1") (pin "C9") (pinfunction "GPIO53_C9") (pintype "bidirectional"))
    )
    (net (code "25") (name "AP4_GP55{slash}TT_BUZZER_GATE") (class "Default")
      (node (ref "P33") (pin "P$1") (pinfunction "P$1_P$1") (pintype "bidirectional"))
      (node (ref "P33") (pin "P$2") (pinfunction "P$1_P$2") (pintype "bidirectional"))
      (node (ref "P33") (pin "P$3") (pinfunction "P$1_P$3") (pintype "bidirectional"))
      (node (ref "U1") (pin "D9") (pinfunction "GPIO55_D9") (pintype "bidirectional"))
    )
    (net (code "26") (name "AP4_GP58{slash}TT_~{CHG}") (class "Default")
      (node (ref "P2") (pin "P$1") (pinfunction "P$1_P$1") (pintype "bidirectional"))
      (node (ref "P2") (pin "P$2") (pinfunction "P$1_P$2") (pintype "bidirectional"))
      (node (ref "P2") (pin "P$3") (pinfunction "P$1_P$3") (pintype "bidirectional"))
      (node (ref "U1") (pin "J7") (pinfunction "GPIO58_J7") (pintype "bidirectional"))
    )
    (net (code "27") (name "AP4_GP60{slash}TT_~{PG}") (class "Default")
      (node (ref "P3") (pin "P$1") (pinfunction "P$1_P$1") (pintype "bidirectional"))
      (node (ref "P3") (pin "P$2") (pinfunction "P$1_P$2") (pintype "bidirectional"))
      (node (ref "P3") (pin "P$3") (pinfunction "P$1_P$3") (pintype "bidirectional"))
      (node (ref "U1") (pin "K8") (pinfunction "GPIO60_K8") (pintype "bidirectional"))
    )
    (net (code "28") (name "AP4_GP63") (class "Default")
      (node (ref "P25") (pin "P$1") (pinfunction "P$1_P$1") (pintype "bidirectional"))
      (node (ref "P25") (pin "P$2") (pinfunction "P$1_P$2") (pintype "bidirectional"))
      (node (ref "P25") (pin "P$3") (pinfunction "P$1_P$3") (pintype "bidirectional"))
      (node (ref "U1") (pin "M6") (pinfunction "GPIO63_M6") (pintype "bidirectional"))
    )
    (net (code "29") (name "AP4_GP65{slash}TT_9DOF_~{RESET}") (class "Default")
      (node (ref "P45") (pin "P$1") (pinfunction "P$1_P$1") (pintype "bidirectional"))
      (node (ref "P45") (pin "P$2") (pinfunction "P$1_P$2") (pintype "bidirectional"))
      (node (ref "P45") (pin "P$3") (pinfunction "P$1_P$3") (pintype "bidirectional"))
      (node (ref "U1") (pin "A7") (pinfunction "GPIO65_A7") (pintype "bidirectional"))
    )
    (net (code "30") (name "AP4_GP66{slash}TT_QI_TS_CTRL") (class "Default")
      (node (ref "P44") (pin "P$1") (pinfunction "P$1_P$1") (pintype "bidirectional"))
      (node (ref "P44") (pin "P$2") (pinfunction "P$1_P$2") (pintype "bidirectional"))
      (node (ref "P44") (pin "P$3") (pinfunction "P$1_P$3") (pintype "bidirectional"))
      (node (ref "U1") (pin "A8") (pinfunction "GPIO66_A8") (pintype "bidirectional"))
    )
    (net (code "31") (name "AP4_GP69{slash}TT_FLASH_~{CS}") (class "Default")
      (node (ref "P42") (pin "P$1") (pinfunction "P$1_P$1") (pintype "bidirectional"))
      (node (ref "P42") (pin "P$2") (pinfunction "P$1_P$2") (pintype "bidirectional"))
      (node (ref "P42") (pin "P$3") (pinfunction "P$1_P$3") (pintype "bidirectional"))
      (node (ref "U1") (pin "B8") (pinfunction "GPIO69_B8") (pintype "bidirectional"))
    )
    (net (code "32") (name "AP4_GP72") (class "Default")
      (node (ref "P39") (pin "P$1") (pinfunction "P$1_P$1") (pintype "bidirectional"))
      (node (ref "P39") (pin "P$2") (pinfunction "P$1_P$2") (pintype "bidirectional"))
      (node (ref "P39") (pin "P$3") (pinfunction "P$1_P$3") (pintype "bidirectional"))
      (node (ref "U1") (pin "C8") (pinfunction "GPIO72_C8") (pintype "bidirectional"))
    )
    (net (code "33") (name "AP4_GP79") (class "Default")
      (node (ref "P22") (pin "P$1") (pinfunction "P$1_P$1") (pintype "bidirectional"))
      (node (ref "P22") (pin "P$2") (pinfunction "P$1_P$2") (pintype "bidirectional"))
      (node (ref "P22") (pin "P$3") (pinfunction "P$1_P$3") (pintype "bidirectional"))
      (node (ref "U1") (pin "M11") (pinfunction "GPIO79_M11") (pintype "bidirectional"))
    )
    (net (code "34") (name "AP4_GP80{slash}SWTRACE0") (class "Default")
      (node (ref "J2") (pin "2") (pinfunction "SWDIO_2") (pintype "bidirectional"))
      (node (ref "J2") (pin "B2") (pinfunction "SWDIO_B2") (pintype "bidirectional"))
      (node (ref "U1") (pin "K10") (pinfunction "GPIO80_K10") (pintype "bidirectional"))
    )
    (net (code "35") (name "AP4_GP81{slash}SWTRACE1") (class "Default")
      (node (ref "J2") (pin "4") (pinfunction "SWDCLK_4") (pintype "bidirectional"))
      (node (ref "J2") (pin "B4") (pinfunction "SWDCLK_B4") (pintype "bidirectional"))
      (node (ref "U1") (pin "L10") (pinfunction "GPIO81_L10") (pintype "bidirectional"))
    )
    (net (code "36") (name "AP4_GP82{slash}SWTRACE2") (class "Default")
      (node (ref "J2") (pin "6") (pinfunction "SWO_6") (pintype "bidirectional"))
      (node (ref "J2") (pin "B6") (pinfunction "SWO_B6") (pintype "bidirectional"))
      (node (ref "P18") (pin "P$1") (pinfunction "P$1_P$1") (pintype "bidirectional"))
      (node (ref "P18") (pin "P$2") (pinfunction "P$1_P$2") (pintype "bidirectional"))
      (node (ref "P18") (pin "P$3") (pinfunction "P$1_P$3") (pintype "bidirectional"))
      (node (ref "U1") (pin "L9") (pinfunction "GPIO82_L9") (pintype "bidirectional"))
    )
    (net (code "37") (name "AP4_GP83{slash}SWTRACE3") (class "Default")
      (node (ref "J2") (pin "3") (pinfunction "~{RESET}_3") (pintype "bidirectional"))
      (node (ref "J2") (pin "B3") (pinfunction "~{RESET}_B3") (pintype "bidirectional"))
      (node (ref "P19") (pin "P$1") (pinfunction "P$1_P$1") (pintype "bidirectional"))
      (node (ref "P19") (pin "P$2") (pinfunction "P$1_P$2") (pintype "bidirectional"))
      (node (ref "P19") (pin "P$3") (pinfunction "P$1_P$3") (pintype "bidirectional"))
      (node (ref "U1") (pin "K9") (pinfunction "GPIO83_K9") (pintype "bidirectional"))
    )
    (net (code "38") (name "AP4_GP88") (class "Default")
      (node (ref "P32") (pin "P$1") (pinfunction "P$1_P$1") (pintype "bidirectional"))
      (node (ref "P32") (pin "P$2") (pinfunction "P$1_P$2") (pintype "bidirectional"))
      (node (ref "P32") (pin "P$3") (pinfunction "P$1_P$3") (pintype "bidirectional"))
      (node (ref "U1") (pin "F9") (pinfunction "GPIO88_F9") (pintype "bidirectional"))
    )
    (net (code "39") (name "AP4_SWDCLK") (class "Default")
      (node (ref "J1") (pin "4") (pinfunction "SWDCLK_4") (pintype "bidirectional"))
      (node (ref "J1") (pin "B4") (pinfunction "SWDCLK_B4") (pintype "bidirectional"))
      (node (ref "U1") (pin "K3") (pinfunction "GPIO20_K3") (pintype "bidirectional"))
    )
    (net (code "40") (name "AP4_SWDIO") (class "Default")
      (node (ref "J1") (pin "2") (pinfunction "SWDIO_2") (pintype "bidirectional"))
      (node (ref "J1") (pin "B2") (pinfunction "SWDIO_B2") (pintype "bidirectional"))
      (node (ref "U1") (pin "J3") (pinfunction "GPIO21_J3") (pintype "bidirectional"))
    )
    (net (code "41") (name "AP4_SWO") (class "Default")
      (node (ref "J1") (pin "6") (pinfunction "SWO_6") (pintype "bidirectional"))
      (node (ref "J1") (pin "B6") (pinfunction "SWO_B6") (pintype "bidirectional"))
      (node (ref "U1") (pin "L4") (pinfunction "GPIO3_L4") (pintype "bidirectional"))
    )
    (net (code "42") (name "AP4_SWTRACECLK") (class "Default")
      (node (ref "J2") (pin "1") (pinfunction "VTREF_1") (pintype "bidirectional"))
      (node (ref "J2") (pin "B1") (pinfunction "VTREF_B1") (pintype "bidirectional"))
      (node (ref "U1") (pin "F12") (pinfunction "GPIO38_F12") (pintype "bidirectional"))
    )
    (net (code "43") (name "AP4_USB0_N") (class "Default")
      (node (ref "P21") (pin "P$1") (pinfunction "P$1_P$1") (pintype "bidirectional"))
      (node (ref "P21") (pin "P$2") (pinfunction "P$1_P$2") (pintype "bidirectional"))
      (node (ref "P21") (pin "P$3") (pinfunction "P$1_P$3") (pintype "bidirectional"))
      (node (ref "U1") (pin "M8") (pinfunction "USB0PN_M8") (pintype "bidirectional"))
    )
    (net (code "44") (name "AP4_USB0_P") (class "Default")
      (node (ref "P20") (pin "P$1") (pinfunction "P$1_P$1") (pintype "bidirectional"))
      (node (ref "P20") (pin "P$2") (pinfunction "P$1_P$2") (pintype "bidirectional"))
      (node (ref "P20") (pin "P$3") (pinfunction "P$1_P$3") (pintype "bidirectional"))
      (node (ref "U1") (pin "M7") (pinfunction "USB0PP_M7") (pintype "bidirectional"))
    )
    (net (code "45") (name "AP4_VDDBH") (class "Default")
      (node (ref "C25") (pin "1") (pinfunction "1_1") (pintype "bidirectional"))
      (node (ref "L2") (pin "2") (pinfunction "2_2") (pintype "bidirectional"))
      (node (ref "RZ1") (pin "1") (pinfunction "1_1") (pintype "passive"))
      (node (ref "TP1") (pin "P$1") (pinfunction "TESTPOINT_P$1") (pintype "bidirectional"))
      (node (ref "U1") (pin "G12") (pinfunction "VDDBH--BLE_BUCK_VOUT_G12") (pintype "bidirectional"))
    )
    (net (code "46") (name "AP4_VDDBH_RF") (class "Default")
      (node (ref "C12") (pin "P$1") (pinfunction "1_P$1") (pintype "bidirectional"))
      (node (ref "RZ1") (pin "2") (pinfunction "2_2") (pintype "passive"))
      (node (ref "U1") (pin "J1") (pinfunction "VDDBH_RF--BLE_BUCK_RF_VOUT_J1") (pintype "bidirectional"))
    )
    (net (code "47") (name "AP4_VDDF") (class "Default")
      (node (ref "C19") (pin "P$1") (pinfunction "1_P$1") (pintype "bidirectional"))
      (node (ref "C22") (pin "P$1") (pinfunction "1_P$1") (pintype "bidirectional"))
      (node (ref "TP3") (pin "P$1") (pinfunction "TESTPOINT_P$1") (pintype "bidirectional"))
      (node (ref "U1") (pin "C2") (pinfunction "VDDF-MEM_C2") (pintype "bidirectional"))
    )
    (net (code "48") (name "AP4_VDDMIPI_1P8") (class "Default")
      (node (ref "C14") (pin "P$1") (pinfunction "1_P$1") (pintype "bidirectional"))
      (node (ref "P28") (pin "P$1") (pinfunction "P$1_P$1") (pintype "bidirectional"))
      (node (ref "P28") (pin "P$2") (pinfunction "P$1_P$2") (pintype "bidirectional"))
      (node (ref "P28") (pin "P$3") (pinfunction "P$1_P$3") (pintype "bidirectional"))
      (node (ref "RZ4") (pin "1") (pinfunction "1_1") (pintype "passive"))
      (node (ref "U1") (pin "H10") (pinfunction "VDD18-MIPI_H10") (pintype "bidirectional"))
    )
    (net (code "49") (name "AP4_VDDUSB_0P9") (class "Default")
      (node (ref "C24") (pin "P$1") (pinfunction "1_P$1") (pintype "bidirectional"))
      (node (ref "P26") (pin "P$1") (pinfunction "P$1_P$1") (pintype "bidirectional"))
      (node (ref "P26") (pin "P$2") (pinfunction "P$1_P$2") (pintype "bidirectional"))
      (node (ref "P26") (pin "P$3") (pinfunction "P$1_P$3") (pintype "bidirectional"))
      (node (ref "RZ2") (pin "1") (pinfunction "1_1") (pintype "passive"))
      (node (ref "U1") (pin "L7") (pinfunction "VDDUSB0P9_L7") (pintype "bidirectional"))
    )
    (net (code "50") (name "AP4_VDDUSB_3P3") (class "Default")
      (node (ref "C13") (pin "P$1") (pinfunction "1_P$1") (pintype "bidirectional"))
      (node (ref "P27") (pin "P$1") (pinfunction "P$1_P$1") (pintype "bidirectional"))
      (node (ref "P27") (pin "P$2") (pinfunction "P$1_P$2") (pintype "bidirectional"))
      (node (ref "P27") (pin "P$3") (pinfunction "P$1_P$3") (pintype "bidirectional"))
      (node (ref "RZ3") (pin "1") (pinfunction "1_1") (pintype "passive"))
      (node (ref "U1") (pin "K7") (pinfunction "VDDUSB33_K7") (pintype "bidirectional"))
    )
    (net (code "51") (name "AP4_~{RESET}") (class "Default")
      (node (ref "C4") (pin "1") (pinfunction "1_1") (pintype "passive"))
      (node (ref "D1") (pin "1") (pinfunction "C_1") (pintype "passive"))
      (node (ref "J1") (pin "3") (pinfunction "~{RESET}_3") (pintype "bidirectional"))
      (node (ref "J1") (pin "B3") (pinfunction "~{RESET}_B3") (pintype "bidirectional"))
      (node (ref "P38") (pin "P$1") (pinfunction "P$1_P$1") (pintype "bidirectional"))
      (node (ref "P38") (pin "P$2") (pinfunction "P$1_P$2") (pintype "bidirectional"))
      (node (ref "P38") (pin "P$3") (pinfunction "P$1_P$3") (pintype "bidirectional"))
      (node (ref "SJ1") (pin "2") (pinfunction "2_2") (pintype "passive"))
      (node (ref "U1") (pin "A6") (pinfunction "~{RST}_A6") (pintype "input"))
    )
    (net (code "52") (name "BLE_RFOUT") (class "Default")
      (node (ref "L4") (pin "2") (pinfunction "2_2") (pintype "passive"))
      (node (ref "P15") (pin "P$1") (pinfunction "P$1_P$1") (pintype "bidirectional"))
      (node (ref "P15") (pin "P$2") (pinfunction "P$1_P$2") (pintype "bidirectional"))
      (node (ref "P15") (pin "P$3") (pinfunction "P$1_P$3") (pintype "bidirectional"))
    )
    (net (code "53") (name "GND") (class "Default")
      (node (ref "C10") (pin "P$2") (pinfunction "2_P$2") (pintype "bidirectional"))
      (node (ref "C11") (pin "P$1") (pinfunction "1_P$1") (pintype "bidirectional"))
      (node (ref "C13") (pin "P$2") (pinfunction "2_P$2") (pintype "bidirectional"))
      (node (ref "C14") (pin "P$2") (pinfunction "2_P$2") (pintype "bidirectional"))
      (node (ref "C15") (pin "P$2") (pinfunction "2_P$2") (pintype "bidirectional"))
      (node (ref "C16") (pin "P$2") (pinfunction "2_P$2") (pintype "bidirectional"))
      (node (ref "C17") (pin "P$2") (pinfunction "2_P$2") (pintype "bidirectional"))
      (node (ref "C18") (pin "P$2") (pinfunction "2_P$2") (pintype "bidirectional"))
      (node (ref "C19") (pin "P$2") (pinfunction "2_P$2") (pintype "bidirectional"))
      (node (ref "C2") (pin "2") (pinfunction "2_2") (pintype "passive"))
      (node (ref "C20") (pin "P$2") (pinfunction "2_P$2") (pintype "bidirectional"))
      (node (ref "C21") (pin "P$2") (pinfunction "2_P$2") (pintype "bidirectional"))
      (node (ref "C23") (pin "P$1") (pinfunction "1_P$1") (pintype "bidirectional"))
      (node (ref "C24") (pin "P$2") (pinfunction "2_P$2") (pintype "bidirectional"))
      (node (ref "C25") (pin "2") (pinfunction "2_2") (pintype "bidirectional"))
      (node (ref "C3") (pin "2") (pinfunction "2_2") (pintype "passive"))
      (node (ref "C4") (pin "2") (pinfunction "2_2") (pintype "passive"))
      (node (ref "C5") (pin "P$2") (pinfunction "2_P$2") (pintype "bidirectional"))
      (node (ref "C6") (pin "P$2") (pinfunction "2_P$2") (pintype "bidirectional"))
      (node (ref "C7") (pin "P$2") (pinfunction "2_P$2") (pintype "bidirectional"))
      (node (ref "C8") (pin "P$2") (pinfunction "2_P$2") (pintype "bidirectional"))
      (node (ref "C9") (pin "P$2") (pinfunction "2_P$2") (pintype "bidirectional"))
      (node (ref "CX1") (pin "2") (pinfunction "2_2") (pintype "passive"))
      (node (ref "CX2") (pin "2") (pinfunction "2_2") (pintype "passive"))
      (node (ref "D1") (pin "2") (pinfunction "A_2") (pintype "passive"))
      (node (ref "J1") (pin "5") (pinfunction "GND_5") (pintype "bidirectional"))
      (node (ref "J1") (pin "B5") (pinfunction "GND_B5") (pintype "bidirectional"))
      (node (ref "J2") (pin "5") (pinfunction "GND_5") (pintype "bidirectional"))
      (node (ref "J2") (pin "B5") (pinfunction "GND_B5") (pintype "bidirectional"))
      (node (ref "P13") (pin "P$1") (pinfunction "P$1_P$1") (pintype "bidirectional"))
      (node (ref "P13") (pin "P$2") (pinfunction "P$1_P$2") (pintype "bidirectional"))
      (node (ref "P13") (pin "P$3") (pinfunction "P$1_P$3") (pintype "bidirectional"))
      (node (ref "P37") (pin "P$1") (pinfunction "P$1_P$1") (pintype "bidirectional"))
      (node (ref "P37") (pin "P$2") (pinfunction "P$1_P$2") (pintype "bidirectional"))
      (node (ref "P37") (pin "P$3") (pinfunction "P$1_P$3") (pintype "bidirectional"))
      (node (ref "RZ2") (pin "2") (pinfunction "2_2") (pintype "passive"))
      (node (ref "RZ3") (pin "2") (pinfunction "2_2") (pintype "passive"))
      (node (ref "RZ4") (pin "2") (pinfunction "2_2") (pintype "passive"))
      (node (ref "SJ1") (pin "1") (pinfunction "1_1") (pintype "passive"))
      (node (ref "U1") (pin "B12") (pinfunction "VSSAUDA_B12") (pintype "bidirectional"))
      (node (ref "U1") (pin "B2") (pinfunction "VSSP-BUCK_REGS_GND_B2") (pintype "bidirectional"))
      (node (ref "U1") (pin "B5") (pinfunction "VSSA-ANALOG_GND_B5") (pintype "bidirectional"))
      (node (ref "U1") (pin "D2") (pinfunction "VSS-DGND_FOR_VDDF_AND_PADS_D2") (pintype "bidirectional"))
      (node (ref "U1") (pin "E12") (pinfunction "VSSAUDD_E12") (pintype "bidirectional"))
      (node (ref "U1") (pin "H1") (pinfunction "VSSB-BLE_UNREG_GND_H1") (pintype "bidirectional"))
      (node (ref "U1") (pin "J10") (pinfunction "VSS18-MIPI_J10") (pintype "bidirectional"))
      (node (ref "U1") (pin "L1") (pinfunction "VSSVCO-BLECORE_GND_FOR_VCO_L1") (pintype "bidirectional"))
      (node (ref "U1") (pin "L2") (pinfunction "VSSS-HVSIMOBUCK_GND_L2") (pintype "bidirectional"))
      (node (ref "U1") (pin "L8") (pinfunction "VSSAUSB_L8") (pintype "bidirectional"))
      (node (ref "VR2") (pin "2") (pinfunction "GND_2") (pintype "bidirectional"))
      (node (ref "VR2") (pin "PAD") (pinfunction "GND_PAD") (pintype "bidirectional"))
      (node (ref "X2") (pin "2") (pinfunction "GND_2") (pintype "bidirectional"))
      (node (ref "X2") (pin "4") (pinfunction "GND_4") (pintype "bidirectional"))
    )
    (net (code "54") (name "Net-(C1-Pad1)") (class "Default")
      (node (ref "C1") (pin "1") (pinfunction "1_1") (pintype "passive"))
      (node (ref "L3") (pin "2") (pinfunction "2_2") (pintype "passive"))
      (node (ref "L4") (pin "1") (pinfunction "1_1") (pintype "passive"))
    )
    (net (code "55") (name "Net-(C6-1)") (class "Default")
      (node (ref "C6") (pin "P$1") (pinfunction "1_P$1") (pintype "bidirectional"))
      (node (ref "RZ6") (pin "1") (pinfunction "1_1") (pintype "passive"))
      (node (ref "VR2") (pin "1") (pinfunction "OUT_1") (pintype "power_in"))
    )
    (net (code "56") (name "Net-(C11-2)") (class "Default")
      (node (ref "C11") (pin "P$2") (pinfunction "2_P$2") (pintype "bidirectional"))
      (node (ref "U1") (pin "A12") (pinfunction "LPADC_VREF_A12") (pintype "bidirectional"))
    )
    (net (code "57") (name "Net-(C16-1)") (class "Default")
      (node (ref "C16") (pin "P$1") (pinfunction "1_P$1") (pintype "bidirectional"))
      (node (ref "U1") (pin "C1") (pinfunction "VDDS-SRAM_HV_SUP_C1") (pintype "bidirectional"))
    )
    (net (code "58") (name "Net-(C17-1)") (class "Default")
      (node (ref "C17") (pin "P$1") (pinfunction "1_P$1") (pintype "bidirectional"))
      (node (ref "U1") (pin "A3") (pinfunction "VDDC-CORE_A3") (pintype "bidirectional"))
    )
    (net (code "59") (name "Net-(C18-1)") (class "Default")
      (node (ref "C18") (pin "P$1") (pinfunction "1_P$1") (pintype "bidirectional"))
      (node (ref "U1") (pin "B3") (pinfunction "VDDC_LV-CORE_LV_B3") (pintype "bidirectional"))
    )
    (net (code "60") (name "Net-(C23-2)") (class "Default")
      (node (ref "C23") (pin "P$2") (pinfunction "2_P$2") (pintype "bidirectional"))
      (node (ref "U1") (pin "B10") (pinfunction "LPMICBIAS_B10") (pintype "output"))
    )
    (net (code "61") (name "Net-(D2-PadC1)") (class "Default")
      (node (ref "D2") (pin "C1") (pinfunction "C1_C1") (pintype "bidirectional"))
      (node (ref "R2") (pin "1") (pinfunction "1_1") (pintype "passive"))
    )
    (net (code "62") (name "Net-(D2-PadC2)") (class "Default")
      (node (ref "D2") (pin "C2") (pinfunction "C2_C2") (pintype "bidirectional"))
      (node (ref "R1") (pin "1") (pinfunction "1_1") (pintype "passive"))
    )
    (net (code "63") (name "Net-(L1-1)") (class "Default")
      (node (ref "L1") (pin "P$1") (pinfunction "1_P$1") (pintype "bidirectional"))
      (node (ref "U1") (pin "A1") (pinfunction "SIMOBUCK_SW_A1") (pintype "bidirectional"))
    )
    (net (code "64") (name "Net-(L1-2)") (class "Default")
      (node (ref "L1") (pin "P$2") (pinfunction "2_P$2") (pintype "bidirectional"))
      (node (ref "U1") (pin "A2") (pinfunction "SIMOBUCK_SWSEL_A2") (pintype "bidirectional"))
    )
    (net (code "65") (name "Net-(U1-RFIOP)") (class "Default")
      (node (ref "CX5") (pin "1") (pinfunction "1_1") (pintype "passive"))
      (node (ref "L3") (pin "1") (pinfunction "1_1") (pintype "passive"))
      (node (ref "U1") (pin "M2") (pinfunction "RFIOP_M2") (pintype "bidirectional"))
    )
    (net (code "66") (name "Net-(U1-VDDBH_SW--BLE_BUCK_SW)") (class "Default")
      (node (ref "L2") (pin "1") (pinfunction "1_1") (pintype "bidirectional"))
      (node (ref "U1") (pin "H12") (pinfunction "VDDBH_SW--BLE_BUCK_SW_H12") (pintype "bidirectional"))
    )
    (net (code "67") (name "Net-(U1-XI)") (class "Default")
      (node (ref "C3") (pin "1") (pinfunction "1_1") (pintype "passive"))
      (node (ref "U1") (pin "A4") (pinfunction "XI_A4") (pintype "bidirectional"))
      (node (ref "X1") (pin "2") (pinfunction "2_2") (pintype "bidirectional"))
    )
    (net (code "68") (name "Net-(U1-XI32M)") (class "Default")
      (node (ref "CX2") (pin "1") (pinfunction "1_1") (pintype "passive"))
      (node (ref "U1") (pin "C12") (pinfunction "XI32M_C12") (pintype "bidirectional"))
      (node (ref "X2") (pin "3") (pinfunction "2_3") (pintype "bidirectional"))
    )
    (net (code "69") (name "Net-(U1-XO)") (class "Default")
      (node (ref "C2") (pin "1") (pinfunction "1_1") (pintype "passive"))
      (node (ref "U1") (pin "A5") (pinfunction "XO_A5") (pintype "bidirectional"))
      (node (ref "X1") (pin "1") (pinfunction "1_1") (pintype "bidirectional"))
    )
    (net (code "70") (name "Net-(U1-XO32M)") (class "Default")
      (node (ref "CX1") (pin "1") (pinfunction "1_1") (pintype "passive"))
      (node (ref "U1") (pin "D12") (pinfunction "XO32M_D12") (pintype "bidirectional"))
      (node (ref "X2") (pin "1") (pinfunction "1_1") (pintype "bidirectional"))
    )
    (net (code "71") (name "Net-(VR2-EN)") (class "Default")
      (node (ref "RZ5") (pin "2") (pinfunction "2_2") (pintype "passive"))
      (node (ref "VR2") (pin "3") (pinfunction "EN_3") (pintype "input"))
    )
    (net (code "72") (name "VDD") (class "Default")
      (node (ref "C5") (pin "P$1") (pinfunction "1_P$1") (pintype "bidirectional"))
      (node (ref "P29") (pin "P$1") (pinfunction "P$1_P$1") (pintype "bidirectional"))
      (node (ref "P29") (pin "P$2") (pinfunction "P$1_P$2") (pintype "bidirectional"))
      (node (ref "P29") (pin "P$3") (pinfunction "P$1_P$3") (pintype "bidirectional"))
      (node (ref "RZ5") (pin "1") (pinfunction "1_1") (pintype "passive"))
      (node (ref "VR2") (pin "4") (pinfunction "IN_4") (pintype "bidirectional"))
    )
    (net (code "73") (name "VDDAUDA_1P8-CLEAN") (class "Default")
      (node (ref "C15") (pin "P$1") (pinfunction "1_P$1") (pintype "bidirectional"))
      (node (ref "RZ6") (pin "2") (pinfunction "2_2") (pintype "passive"))
      (node (ref "U1") (pin "B11") (pinfunction "VDDAUDA_B11") (pintype "bidirectional"))
    )
    (net (code "74") (name "unconnected-(U1-GPIO0-PadH3)") (class "Default")
      (node (ref "U1") (pin "H3") (pinfunction "GPIO0_H3") (pintype "bidirectional"))
    )
    (net (code "75") (name "unconnected-(U1-GPIO1-PadJ4)") (class "Default")
      (node (ref "U1") (pin "J4") (pinfunction "GPIO1_J4") (pintype "bidirectional"))
    )
    (net (code "76") (name "unconnected-(U1-GPIO2-PadK4)") (class "Default")
      (node (ref "U1") (pin "K4") (pinfunction "GPIO2_K4") (pintype "bidirectional"))
    )
    (net (code "77") (name "unconnected-(U1-GPIO4-PadM4)") (class "Default")
      (node (ref "U1") (pin "M4") (pinfunction "GPIO4_M4") (pintype "bidirectional"))
    )
    (net (code "78") (name "unconnected-(U1-GPIO5-PadH4)") (class "Default")
      (node (ref "U1") (pin "H4") (pinfunction "GPIO5_H4") (pintype "bidirectional"))
    )
    (net (code "79") (name "unconnected-(U1-GPIO7-PadJ6)") (class "Default")
      (node (ref "U1") (pin "J6") (pinfunction "GPIO7_J6") (pintype "bidirectional"))
    )
    (net (code "80") (name "unconnected-(U1-GPIO10-PadE6)") (class "Default")
      (node (ref "U1") (pin "E6") (pinfunction "GPIO10_E6") (pintype "bidirectional"))
    )
    (net (code "81") (name "unconnected-(U1-GPIO11-PadE4)") (class "Default")
      (node (ref "U1") (pin "E4") (pinfunction "GPIO11_E4") (pintype "bidirectional"))
    )
    (net (code "82") (name "unconnected-(U1-GPIO12-PadB4)") (class "Default")
      (node (ref "U1") (pin "B4") (pinfunction "GPIO12_B4") (pintype "bidirectional"))
    )
    (net (code "83") (name "unconnected-(U1-GPIO15-PadE5)") (class "Default")
      (node (ref "U1") (pin "E5") (pinfunction "GPIO15_E5") (pintype "bidirectional"))
    )
    (net (code "84") (name "unconnected-(U1-GPIO16-PadD7)") (class "Default")
      (node (ref "U1") (pin "D7") (pinfunction "GPIO16_D7") (pintype "bidirectional"))
    )
    (net (code "85") (name "unconnected-(U1-GPIO19-PadC3)") (class "Default")
      (node (ref "U1") (pin "C3") (pinfunction "GPIO19_C3") (pintype "bidirectional"))
    )
    (net (code "86") (name "unconnected-(U1-GPIO22-PadF3)") (class "Default")
      (node (ref "U1") (pin "F3") (pinfunction "GPIO22_F3") (pintype "bidirectional"))
    )
    (net (code "87") (name "unconnected-(U1-GPIO23-PadF2)") (class "Default")
      (node (ref "U1") (pin "F2") (pinfunction "GPIO23_F2") (pintype "bidirectional"))
    )
    (net (code "88") (name "unconnected-(U1-GPIO28-PadE3)") (class "Default")
      (node (ref "U1") (pin "E3") (pinfunction "GPIO28_E3") (pintype "bidirectional"))
    )
    (net (code "89") (name "unconnected-(U1-GPIO37-PadF11)") (class "Default")
      (node (ref "U1") (pin "F11") (pinfunction "GPIO37_F11") (pintype "bidirectional"))
    )
    (net (code "90") (name "unconnected-(U1-GPIO52-PadC10)") (class "Default")
      (node (ref "U1") (pin "C10") (pinfunction "GPIO52_C10") (pintype "bidirectional"))
    )
    (net (code "91") (name "unconnected-(U1-GPIO54-PadD10)") (class "Default")
      (node (ref "U1") (pin "D10") (pinfunction "GPIO54_D10") (pintype "bidirectional"))
    )
    (net (code "92") (name "unconnected-(U1-GPIO56-PadE10)") (class "Default")
      (node (ref "U1") (pin "E10") (pinfunction "GPIO56_E10") (pintype "bidirectional"))
    )
    (net (code "93") (name "unconnected-(U1-GPIO57-PadE9)") (class "Default")
      (node (ref "U1") (pin "E9") (pinfunction "GPIO57_E9") (pintype "bidirectional"))
    )
    (net (code "94") (name "unconnected-(U1-GPIO59-PadJ8)") (class "Default")
      (node (ref "U1") (pin "J8") (pinfunction "GPIO59_J8") (pintype "bidirectional"))
    )
    (net (code "95") (name "unconnected-(U1-GPIO61-PadK6)") (class "Default")
      (node (ref "U1") (pin "K6") (pinfunction "GPIO61_K6") (pintype "bidirectional"))
    )
    (net (code "96") (name "unconnected-(U1-GPIO62-PadL6)") (class "Default")
      (node (ref "U1") (pin "L6") (pinfunction "GPIO62_L6") (pintype "bidirectional"))
    )
    (net (code "97") (name "unconnected-(U1-GPIO64-PadB6)") (class "Default")
      (node (ref "U1") (pin "B6") (pinfunction "GPIO64_B6") (pintype "bidirectional"))
    )
    (net (code "98") (name "unconnected-(U1-GPIO67-PadC6)") (class "Default")
      (node (ref "U1") (pin "C6") (pinfunction "GPIO67_C6") (pintype "bidirectional"))
    )
    (net (code "99") (name "unconnected-(U1-GPIO68-PadB7)") (class "Default")
      (node (ref "U1") (pin "B7") (pinfunction "GPIO68_B7") (pintype "bidirectional"))
    )
    (net (code "100") (name "unconnected-(U1-GPIO70-PadC5)") (class "Default")
      (node (ref "U1") (pin "C5") (pinfunction "GPIO70_C5") (pintype "bidirectional"))
    )
    (net (code "101") (name "unconnected-(U1-GPIO71-PadC7)") (class "Default")
      (node (ref "U1") (pin "C7") (pinfunction "GPIO71_C7") (pintype "bidirectional"))
    )
    (net (code "102") (name "unconnected-(U1-GPIO73-PadD8)") (class "Default")
      (node (ref "U1") (pin "D8") (pinfunction "GPIO73_D8") (pintype "bidirectional"))
    )
    (net (code "103") (name "unconnected-(U1-GPIO74-PadG11)") (class "Default")
      (node (ref "U1") (pin "G11") (pinfunction "GPIO74_G11") (pintype "bidirectional"))
    )
    (net (code "104") (name "unconnected-(U1-GPIO75-PadH11)") (class "Default")
      (node (ref "U1") (pin "H11") (pinfunction "GPIO75_H11") (pintype "bidirectional"))
    )
    (net (code "105") (name "unconnected-(U1-GPIO76-PadJ11)") (class "Default")
      (node (ref "U1") (pin "J11") (pinfunction "GPIO76_J11") (pintype "bidirectional"))
    )
    (net (code "106") (name "unconnected-(U1-GPIO77-PadK11)") (class "Default")
      (node (ref "U1") (pin "K11") (pinfunction "GPIO77_K11") (pintype "bidirectional"))
    )
    (net (code "107") (name "unconnected-(U1-GPIO78-PadL11)") (class "Default")
      (node (ref "U1") (pin "L11") (pinfunction "GPIO78_L11") (pintype "bidirectional"))
    )
    (net (code "108") (name "unconnected-(U1-GPIO84-PadJ9)") (class "Default")
      (node (ref "U1") (pin "J9") (pinfunction "GPIO84_J9") (pintype "bidirectional"))
    )
    (net (code "109") (name "unconnected-(U1-GPIO85-PadH9)") (class "Default")
      (node (ref "U1") (pin "H9") (pinfunction "GPIO85_H9") (pintype "bidirectional"))
    )
    (net (code "110") (name "unconnected-(U1-GPIO86-PadG10)") (class "Default")
      (node (ref "U1") (pin "G10") (pinfunction "GPIO86_G10") (pintype "bidirectional"))
    )
    (net (code "111") (name "unconnected-(U1-GPIO87-PadG9)") (class "Default")
      (node (ref "U1") (pin "G9") (pinfunction "GPIO87_G9") (pintype "bidirectional"))
    )
    (net (code "112") (name "unconnected-(U1-GPIO89-PadF10)") (class "Default")
      (node (ref "U1") (pin "F10") (pinfunction "GPIO89_F10") (pintype "bidirectional"))
    )
    (net (code "113") (name "unconnected-(U1-GPIO90-PadJ2)") (class "Default")
      (node (ref "U1") (pin "J2") (pinfunction "GPIO90_J2") (pintype "bidirectional"))
    )
    (net (code "114") (name "unconnected-(U1-GPIO91-PadK2)") (class "Default")
      (node (ref "U1") (pin "K2") (pinfunction "GPIO91_K2") (pintype "bidirectional"))
    )
    (net (code "115") (name "unconnected-(U1-LPADC_D0NSE0-PadA10)") (class "Default")
      (node (ref "U1") (pin "A10") (pinfunction "LPADC_D0NSE0_A10") (pintype "input"))
    )
    (net (code "116") (name "unconnected-(U1-LPADC_D0PSE1-PadA11)") (class "Default")
      (node (ref "U1") (pin "A11") (pinfunction "LPADC_D0PSE1_A11") (pintype "input"))
    )
    (net (code "117") (name "unconnected-(U1-LPADC_D1NSE2-PadC11)") (class "Default")
      (node (ref "U1") (pin "C11") (pinfunction "LPADC_D1NSE2_C11") (pintype "input"))
    )
    (net (code "118") (name "unconnected-(U1-LPADC_D1PSE3-PadD11)") (class "Default")
      (node (ref "U1") (pin "D11") (pinfunction "LPADC_D1PSE3_D11") (pintype "input"))
    )
    (net (code "119") (name "unconnected-(U1-MIPI_CLKN-PadJ12)") (class "Default")
      (node (ref "U1") (pin "J12") (pinfunction "MIPI_CLKN_J12") (pintype "bidirectional"))
    )
    (net (code "120") (name "unconnected-(U1-MIPI_CLKP-PadK12)") (class "Default")
      (node (ref "U1") (pin "K12") (pinfunction "MIPI_CLKP_K12") (pintype "bidirectional"))
    )
    (net (code "121") (name "unconnected-(U1-MIPI_DON-PadL12)") (class "Default")
      (node (ref "U1") (pin "L12") (pinfunction "MIPI_DON_L12") (pintype "bidirectional"))
    )
    (net (code "122") (name "unconnected-(U1-MIPI_DOP-PadM12)") (class "Default")
      (node (ref "U1") (pin "M12") (pinfunction "MIPI_DOP_M12") (pintype "bidirectional"))
    )
    (net (code "123") (name "unconnected-(U1-TXEN-PadK1)") (class "Default")
      (node (ref "U1") (pin "K1") (pinfunction "TXEN_K1") (pintype "output"))
    )
  )
)
